# Power_Enable.net
KiCad netlist of a schematic drawn in Altium Designer
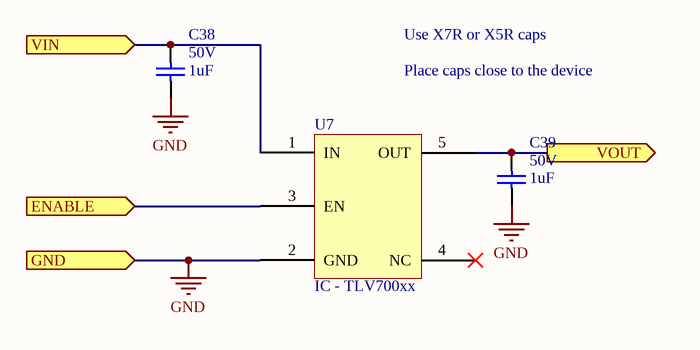
[diagram p0: Power_Enable.SchDoc]

(export (version "E")
  (design (tool "Eeschema 10.0.6"))
  (components
    (comp (ref "C38")
      (value "1uF")
      (footprint "CS-0603")
      (fields
        (field (name "TOLERANCE") "10%")
        (field (name "VOLTAGE") "50V")
        (field (name "Comment") "CS - CAPACITOR")
      )
      (libsource (lib "CHINOOK_LIBRARY") (part "CS - CAPACITOR"))
    )
    (comp (ref "C39")
      (value "1uF")
      (footprint "CS-0603")
      (fields
        (field (name "TOLERANCE") "10%")
        (field (name "VOLTAGE") "50V")
        (field (name "Comment") "CS - CAPACITOR")
      )
      (libsource (lib "CHINOOK_LIBRARY") (part "CS - CAPACITOR"))
    )
    (comp (ref "U7")
      (value "IC - TLV700xx")
      (footprint "IC-SOT-23-5")
      (description "LDO")
      (libsource (lib "CHINOOK_LIBRARY") (part "IC - TLV700xx"))
    )
  )
  (nets
    (net (code "1") (name "/ENABLE") (class "Default")
      (node (ref "U7") (pin "3") (pinfunction "EN_3") (pintype "passive"))
    )
    (net (code "2") (name "/VIN") (class "Default")
      (node (ref "C38") (pin "2") (pinfunction "2_2") (pintype "passive"))
      (node (ref "U7") (pin "1") (pinfunction "IN_1") (pintype "passive"))
    )
    (net (code "3") (name "/VOUT") (class "Default")
      (node (ref "C39") (pin "2") (pinfunction "2_2") (pintype "passive"))
      (node (ref "U7") (pin "5") (pinfunction "OUT_5") (pintype "passive"))
    )
    (net (code "4") (name "GND") (class "Default")
      (node (ref "C38") (pin "1") (pinfunction "1_1") (pintype "passive"))
      (node (ref "C39") (pin "1") (pinfunction "1_1") (pintype "passive"))
      (node (ref "U7") (pin "2") (pinfunction "GND_2") (pintype "passive"))
    )
    (net (code "5") (name "unconnected-(U7-NC-Pad4)") (class "Default")
      (node (ref "U7") (pin "4") (pinfunction "NC_4") (pintype "passive+no_connect"))
    )
  )
)
